# plugV15-smd-5x5cm-no-screen-value.net
KiCad netlist of a schematic drawn in EAGLE
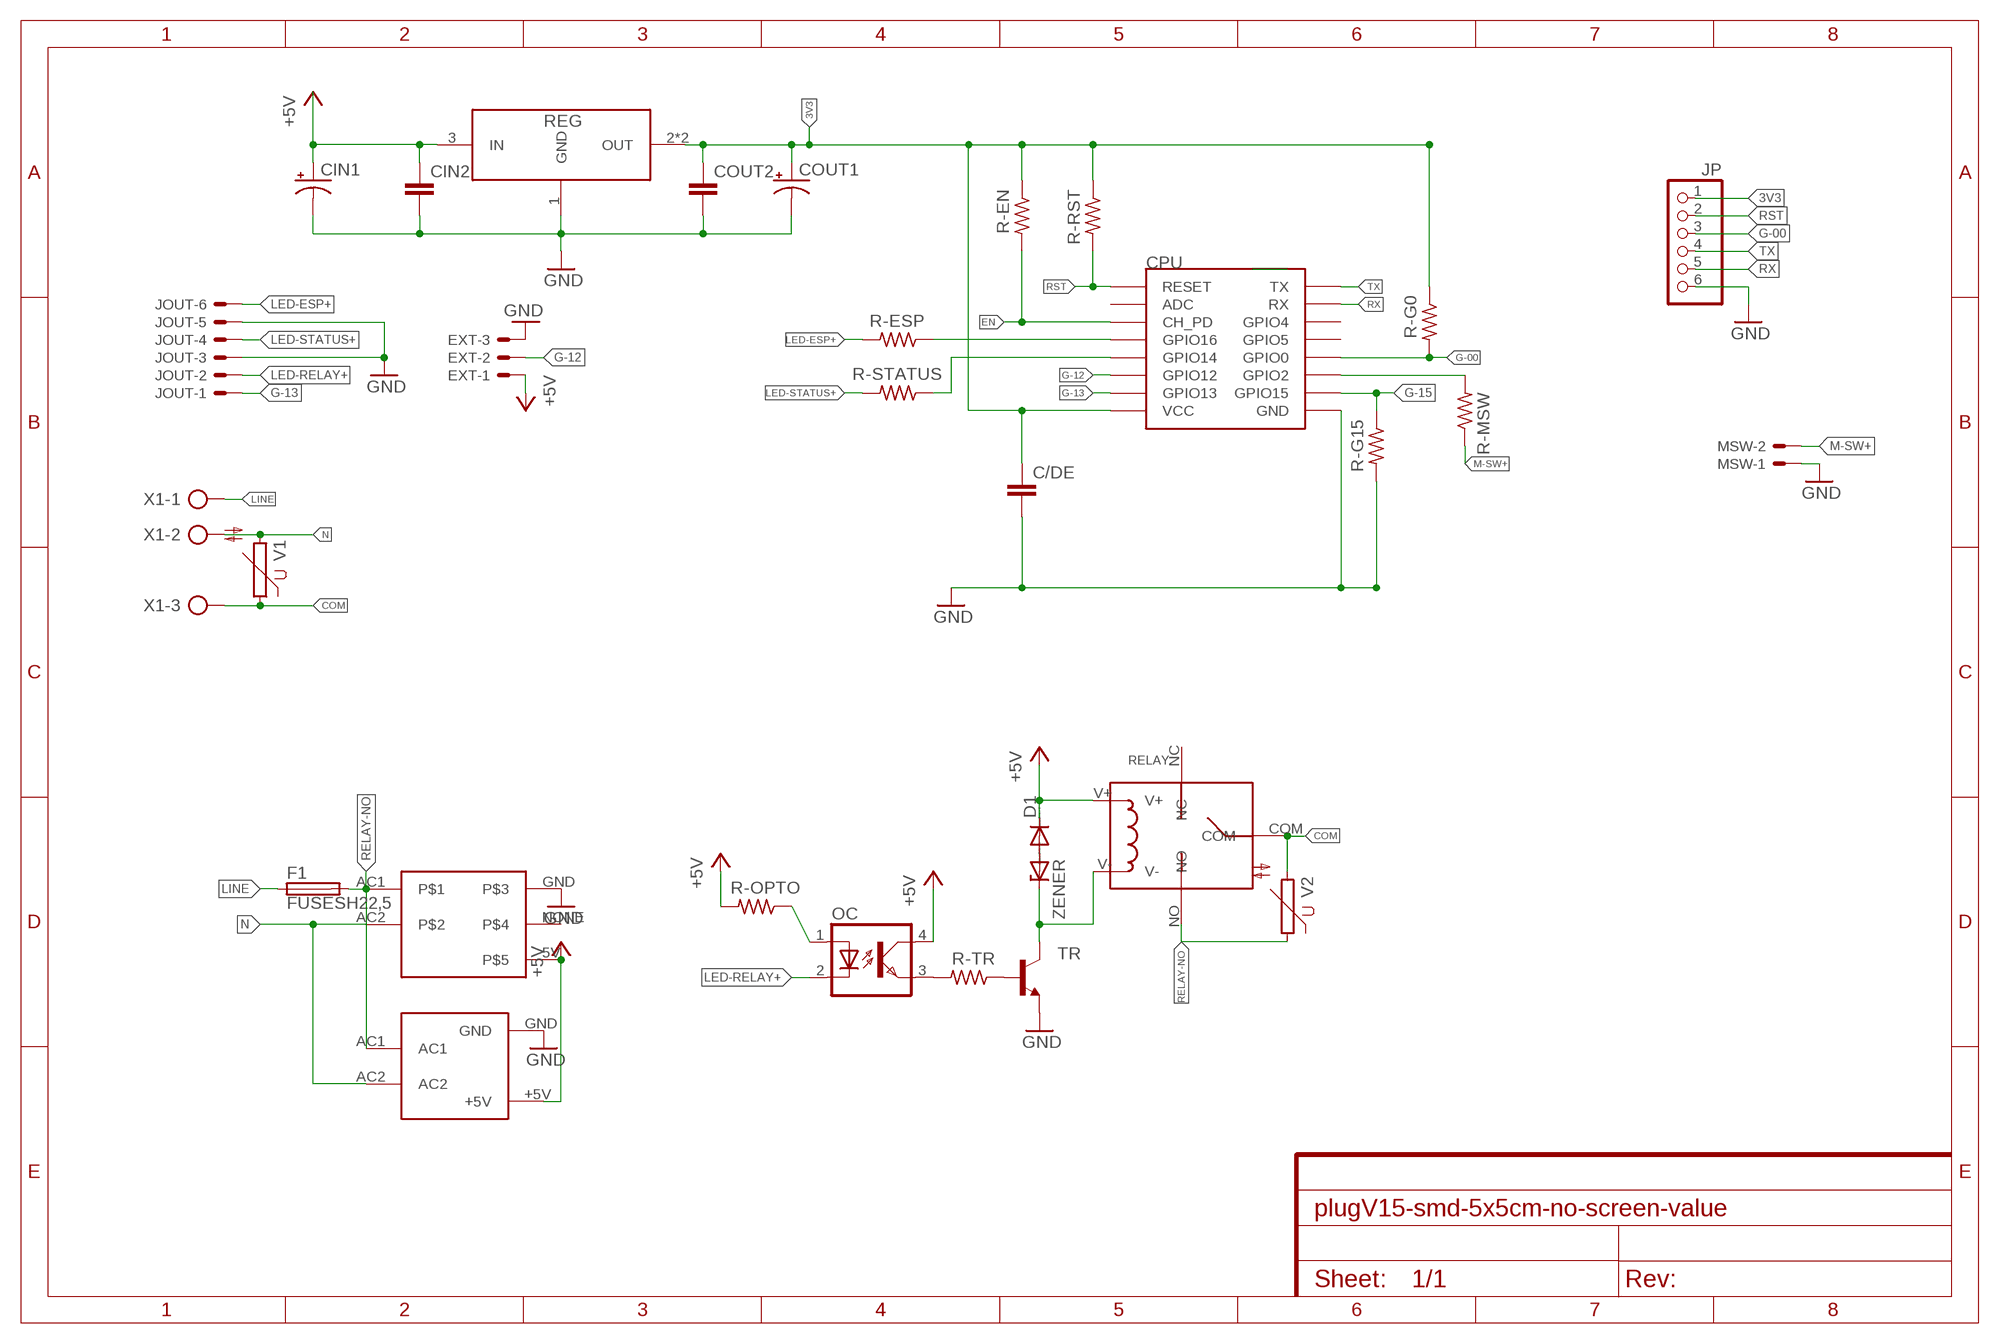
[diagram p0: schematic, sheet 1]

(export (version "E")
  (design (tool "Eeschema 10.0.6"))
  (components
    (comp (ref "C/DE")
      (value "C-EUC0805")
      (footprint "eagle-import:C0805")
      (libsource (lib "eagle-import") (part "C-EUC0805"))
    )
    (comp (ref "CIN1")
      (value "CPOL-USE2.5-5")
      (footprint "eagle-import:E2,5-5")
      (libsource (lib "eagle-import") (part "CPOL-USE2.5-5"))
    )
    (comp (ref "CIN2")
      (value "C-EUC0805")
      (footprint "eagle-import:C0805")
      (libsource (lib "eagle-import") (part "C-EUC0805"))
    )
    (comp (ref "COUT1")
      (value "CPOL-USE2.5-5")
      (footprint "eagle-import:E2,5-5")
      (libsource (lib "eagle-import") (part "CPOL-USE2.5-5"))
    )
    (comp (ref "COUT2")
      (value "C-EUC0805")
      (footprint "eagle-import:C0805")
      (libsource (lib "eagle-import") (part "C-EUC0805"))
    )
    (comp (ref "CPU")
      (value "ESP12SMD")
      (footprint "eagle-import:ESP12-SMD")
      (libsource (lib "eagle-import") (part "ESP12SMD"))
    )
    (comp (ref "D1")
      (value "1N4148DO35-7")
      (footprint "eagle-import:DO35-7")
      (libsource (lib "eagle-import") (part "1N4148DO35-7"))
    )
    (comp (ref "EXT")
      (value "53048-03")
      (footprint "eagle-import:53048-03")
      (fields (field (name "MF") "WALDOM/MOLEX") (field (name "MPN") "53048-0310"))
      (libsource (lib "eagle-import") (part "53?-03048"))
    )
    (comp (ref "F1")
      (value "FUSESH22,5")
      (footprint "eagle-import:SH22,5")
      (libsource (lib "eagle-import") (part "FUSESH22,5"))
    )
    (comp (ref "HLK")
      (value "HLK-PM01")
      (footprint "eagle-import:HLK-PM01")
      (libsource (lib "eagle-import") (part "HLK-PM01"))
    )
    (comp (ref "JOUT")
      (value "53048-06")
      (footprint "eagle-import:53048-06")
      (fields (field (name "MF") "WALDOM/MOLEX") (field (name "MPN") "53048-0610"))
      (libsource (lib "eagle-import") (part "53?-06048"))
    )
    (comp (ref "JP")
      (value "PINHD-1X6")
      (footprint "eagle-import:1X06")
      (libsource (lib "eagle-import") (part "PINHD-1X6"))
    )
    (comp (ref "MSW")
      (value "53048-02")
      (footprint "eagle-import:53048-02")
      (fields (field (name "MF") "MOLEX") (field (name "MPN") "53048-0210"))
      (libsource (lib "eagle-import") (part "53?-02048"))
    )
    (comp (ref "OC")
      (value "PC817")
      (footprint "eagle-import:DIL04")
      (fields (field (name "MPN") "PC817X4J000F"))
      (libsource (lib "eagle-import") (part "PC817"))
    )
    (comp (ref "R-EN")
      (value "R-US_M0805")
      (footprint "eagle-import:M0805")
      (libsource (lib "eagle-import") (part "R-US_M0805"))
    )
    (comp (ref "R-ESP")
      (value "R-US_M0805")
      (footprint "eagle-import:M0805")
      (libsource (lib "eagle-import") (part "R-US_M0805"))
    )
    (comp (ref "R-G0")
      (value "R-US_M0805")
      (footprint "eagle-import:M0805")
      (libsource (lib "eagle-import") (part "R-US_M0805"))
    )
    (comp (ref "R-G15")
      (value "R-US_M0805")
      (footprint "eagle-import:M0805")
      (libsource (lib "eagle-import") (part "R-US_M0805"))
    )
    (comp (ref "R-MSW")
      (value "R-US_M0805")
      (footprint "eagle-import:M0805")
      (libsource (lib "eagle-import") (part "R-US_M0805"))
    )
    (comp (ref "R-OPTO")
      (value "R-US_M0805")
      (footprint "eagle-import:M0805")
      (libsource (lib "eagle-import") (part "R-US_M0805"))
    )
    (comp (ref "R-RST")
      (value "R-US_M0805")
      (footprint "eagle-import:M0805")
      (libsource (lib "eagle-import") (part "R-US_M0805"))
    )
    (comp (ref "R-STATUS")
      (value "R-US_M0805")
      (footprint "eagle-import:M0805")
      (libsource (lib "eagle-import") (part "R-US_M0805"))
    )
    (comp (ref "R-TR")
      (value "R-US_M0805")
      (footprint "eagle-import:M0805")
      (libsource (lib "eagle-import") (part "R-US_M0805"))
    )
    (comp (ref "REG")
      (value "AMS1117-3.3")
      (footprint "eagle-import:SOT-223")
      (libsource (lib "eagle-import") (part "AMS1117-3.3"))
    )
    (comp (ref "RELAY")
      (value "RELAY-SONGLE")
      (footprint "eagle-import:RELAY-SONGLE")
      (libsource (lib "eagle-import") (part "RELAY-SONGLE"))
    )
    (comp (ref "TR")
      (value "BC817-16SMD")
      (footprint "eagle-import:SOT23-BEC")
      (libsource (lib "eagle-import") (part "BC817SMD-16"))
    )
    (comp (ref "U$4")
      (value "POWERSUPPLY-5V-700MA")
      (footprint "eagle-import:POWERSUPPLY-5V-700MA")
      (libsource (lib "eagle-import") (part "POWERSUPPLY-5V-700MA"))
    )
    (comp (ref "V1")
      (value "S14K11")
      (footprint "eagle-import:S14K11")
      (libsource (lib "eagle-import") (part "S14K11"))
    )
    (comp (ref "V2")
      (value "S14K11")
      (footprint "eagle-import:S14K11")
      (libsource (lib "eagle-import") (part "S14K11"))
    )
    (comp (ref "X1")
      (value "AK300/3")
      (footprint "eagle-import:AK300_3")
      (libsource (lib "eagle-import") (part "AK300/3"))
    )
    (comp (ref "ZENER")
      (value "1N4728")
      (footprint "eagle-import:DO41Z10")
      (libsource (lib "eagle-import") (part "1N4728"))
    )
  )
  (nets
    (net (code "1") (name "+5V") (class "Default")
      (node (ref "CIN1") (pin "+") (pinfunction "+_+") (pintype "passive"))
      (node (ref "CIN2") (pin "1") (pinfunction "1_1") (pintype "passive"))
      (node (ref "D1") (pin "C") (pinfunction "C_C") (pintype "passive"))
      (node (ref "EXT") (pin "1") (pinfunction "S_1") (pintype "passive"))
      (node (ref "HLK") (pin "+5V") (pinfunction "+5V_+5V") (pintype "bidirectional"))
      (node (ref "OC") (pin "4") (pinfunction "COL_4") (pintype "passive"))
      (node (ref "R-OPTO") (pin "2") (pinfunction "2_2") (pintype "passive"))
      (node (ref "REG") (pin "3") (pinfunction "IN_3") (pintype "input"))
      (node (ref "RELAY") (pin "V+") (pinfunction "V+_V+") (pintype "bidirectional"))
      (node (ref "U$4") (pin "5V") (pinfunction "P$5_5V") (pintype "bidirectional"))
    )
    (net (code "2") (name "3V3") (class "Default")
      (node (ref "C/DE") (pin "1") (pinfunction "1_1") (pintype "passive"))
      (node (ref "COUT1") (pin "+") (pinfunction "+_+") (pintype "passive"))
      (node (ref "COUT2") (pin "1") (pinfunction "1_1") (pintype "passive"))
      (node (ref "CPU") (pin "VCC") (pinfunction "VCC_VCC") (pintype "bidirectional"))
      (node (ref "JP") (pin "1") (pinfunction "1_1") (pintype "passive"))
      (node (ref "R-EN") (pin "1") (pinfunction "1_1") (pintype "passive"))
      (node (ref "R-G0") (pin "1") (pinfunction "1_1") (pintype "passive"))
      (node (ref "R-RST") (pin "1") (pinfunction "1_1") (pintype "passive"))
      (node (ref "REG") (pin "2") (pinfunction "OUT_2") (pintype "output"))
      (node (ref "REG") (pin "4") (pinfunction "OUT_4") (pintype "output"))
    )
    (net (code "3") (name "COM") (class "Default")
      (node (ref "RELAY") (pin "COM") (pinfunction "COM_COM") (pintype "bidirectional"))
      (node (ref "V1") (pin "1") (pinfunction "1_1") (pintype "passive"))
      (node (ref "V2") (pin "2") (pinfunction "2_2") (pintype "passive"))
      (node (ref "X1") (pin "3") (pinfunction "KL_3") (pintype "passive"))
    )
    (net (code "4") (name "EN") (class "Default")
      (node (ref "CPU") (pin "CH_PD") (pinfunction "CH_PD_CH_PD") (pintype "bidirectional"))
      (node (ref "R-EN") (pin "2") (pinfunction "2_2") (pintype "passive"))
    )
    (net (code "5") (name "G-00") (class "Default")
      (node (ref "CPU") (pin "GPIO0") (pinfunction "GPIO0_GPIO0") (pintype "bidirectional"))
      (node (ref "JP") (pin "3") (pinfunction "3_3") (pintype "passive"))
      (node (ref "R-G0") (pin "2") (pinfunction "2_2") (pintype "passive"))
    )
    (net (code "6") (name "G-12") (class "Default")
      (node (ref "CPU") (pin "GPIO12") (pinfunction "GPIO12_GPIO12") (pintype "bidirectional"))
      (node (ref "EXT") (pin "2") (pinfunction "S_2") (pintype "passive"))
    )
    (net (code "7") (name "G-13") (class "Default")
      (node (ref "CPU") (pin "GPIO13") (pinfunction "GPIO13_GPIO13") (pintype "bidirectional"))
      (node (ref "JOUT") (pin "1") (pinfunction "S_1") (pintype "passive"))
    )
    (net (code "8") (name "G-15") (class "Default")
      (node (ref "CPU") (pin "GPIO15") (pinfunction "GPIO15_GPIO15") (pintype "bidirectional"))
      (node (ref "R-G15") (pin "1") (pinfunction "1_1") (pintype "passive"))
    )
    (net (code "9") (name "GND") (class "Default")
      (node (ref "C/DE") (pin "2") (pinfunction "2_2") (pintype "passive"))
      (node (ref "CIN1") (pin "-") (pinfunction "-_-") (pintype "passive"))
      (node (ref "CIN2") (pin "2") (pinfunction "2_2") (pintype "passive"))
      (node (ref "COUT1") (pin "-") (pinfunction "-_-") (pintype "passive"))
      (node (ref "COUT2") (pin "2") (pinfunction "2_2") (pintype "passive"))
      (node (ref "CPU") (pin "GND") (pinfunction "GND_GND") (pintype "bidirectional"))
      (node (ref "EXT") (pin "3") (pinfunction "S_3") (pintype "passive"))
      (node (ref "HLK") (pin "GND") (pinfunction "GND_GND") (pintype "bidirectional"))
      (node (ref "JOUT") (pin "3") (pinfunction "S_3") (pintype "passive"))
      (node (ref "JOUT") (pin "5") (pinfunction "S_5") (pintype "passive"))
      (node (ref "JP") (pin "6") (pinfunction "6_6") (pintype "passive"))
      (node (ref "MSW") (pin "1") (pinfunction "S_1") (pintype "passive"))
      (node (ref "R-G15") (pin "2") (pinfunction "2_2") (pintype "passive"))
      (node (ref "REG") (pin "1") (pinfunction "GND_1") (pintype "passive"))
      (node (ref "TR") (pin "E") (pinfunction "E_E") (pintype "passive"))
      (node (ref "U$4") (pin "GND") (pinfunction "P$3_GND") (pintype "bidirectional"))
    )
    (net (code "10") (name "LED-ESP+") (class "Default")
      (node (ref "JOUT") (pin "6") (pinfunction "S_6") (pintype "passive"))
      (node (ref "R-ESP") (pin "2") (pinfunction "2_2") (pintype "passive"))
    )
    (net (code "11") (name "LED-RELAY+") (class "Default")
      (node (ref "JOUT") (pin "2") (pinfunction "S_2") (pintype "passive"))
      (node (ref "OC") (pin "2") (pinfunction "C_2") (pintype "passive"))
    )
    (net (code "12") (name "LED-STATUS+") (class "Default")
      (node (ref "JOUT") (pin "4") (pinfunction "S_4") (pintype "passive"))
      (node (ref "R-STATUS") (pin "2") (pinfunction "2_2") (pintype "passive"))
    )
    (net (code "13") (name "LINE") (class "Default")
      (node (ref "F1") (pin "1") (pinfunction "1_1") (pintype "passive"))
      (node (ref "X1") (pin "1") (pinfunction "KL_1") (pintype "passive"))
    )
    (net (code "14") (name "M-SW+") (class "Default")
      (node (ref "MSW") (pin "2") (pinfunction "S_2") (pintype "passive"))
      (node (ref "R-MSW") (pin "1") (pinfunction "1_1") (pintype "passive"))
    )
    (net (code "15") (name "N") (class "Default")
      (node (ref "HLK") (pin "AC2") (pinfunction "AC2_AC2") (pintype "bidirectional"))
      (node (ref "U$4") (pin "AC2") (pinfunction "P$2_AC2") (pintype "bidirectional"))
      (node (ref "V1") (pin "2") (pinfunction "2_2") (pintype "passive"))
      (node (ref "X1") (pin "2") (pinfunction "KL_2") (pintype "passive"))
    )
    (net (code "16") (name "Net-(CPU-PadGPIO2)") (class "Default")
      (node (ref "CPU") (pin "GPIO2") (pinfunction "GPIO2_GPIO2") (pintype "bidirectional"))
      (node (ref "R-MSW") (pin "2") (pinfunction "2_2") (pintype "passive"))
    )
    (net (code "17") (name "Net-(CPU-PadGPIO14)") (class "Default")
      (node (ref "CPU") (pin "GPIO14") (pinfunction "GPIO14_GPIO14") (pintype "bidirectional"))
      (node (ref "R-STATUS") (pin "1") (pinfunction "1_1") (pintype "passive"))
    )
    (net (code "18") (name "Net-(CPU-PadGPIO16)") (class "Default")
      (node (ref "CPU") (pin "GPIO16") (pinfunction "GPIO16_GPIO16") (pintype "bidirectional"))
      (node (ref "R-ESP") (pin "1") (pinfunction "1_1") (pintype "passive"))
    )
    (net (code "19") (name "Net-(D1-PadA)") (class "Default")
      (node (ref "D1") (pin "A") (pinfunction "A_A") (pintype "passive"))
      (node (ref "ZENER") (pin "A") (pinfunction "A_A") (pintype "passive"))
    )
    (net (code "20") (name "Net-(OC-A)") (class "Default")
      (node (ref "OC") (pin "1") (pinfunction "A_1") (pintype "passive"))
      (node (ref "R-OPTO") (pin "1") (pinfunction "1_1") (pintype "passive"))
    )
    (net (code "21") (name "Net-(OC-EMIT)") (class "Default")
      (node (ref "OC") (pin "3") (pinfunction "EMIT_3") (pintype "passive"))
      (node (ref "R-TR") (pin "2") (pinfunction "2_2") (pintype "passive"))
    )
    (net (code "22") (name "Net-(R-TR-Pad1)") (class "Default")
      (node (ref "R-TR") (pin "1") (pinfunction "1_1") (pintype "passive"))
      (node (ref "TR") (pin "B") (pinfunction "B_B") (pintype "passive"))
    )
    (net (code "23") (name "Net-(RELAY-PadV-)") (class "Default")
      (node (ref "RELAY") (pin "V-") (pinfunction "V-_V-") (pintype "bidirectional"))
      (node (ref "TR") (pin "C") (pinfunction "C_C") (pintype "passive"))
      (node (ref "ZENER") (pin "C") (pinfunction "C_C") (pintype "passive"))
    )
    (net (code "24") (name "RELAY-NO") (class "Default")
      (node (ref "F1") (pin "2") (pinfunction "2_2") (pintype "passive"))
      (node (ref "HLK") (pin "AC1") (pinfunction "AC1_AC1") (pintype "bidirectional"))
      (node (ref "RELAY") (pin "NO") (pinfunction "NO_NO") (pintype "bidirectional"))
      (node (ref "U$4") (pin "AC1") (pinfunction "P$1_AC1") (pintype "bidirectional"))
      (node (ref "V2") (pin "1") (pinfunction "1_1") (pintype "passive"))
    )
    (net (code "25") (name "RST") (class "Default")
      (node (ref "CPU") (pin "RESET") (pinfunction "RESET_RESET") (pintype "bidirectional"))
      (node (ref "JP") (pin "2") (pinfunction "2_2") (pintype "passive"))
      (node (ref "R-RST") (pin "2") (pinfunction "2_2") (pintype "passive"))
    )
    (net (code "26") (name "RX") (class "Default")
      (node (ref "CPU") (pin "RXD0") (pinfunction "RX_RXD0") (pintype "bidirectional"))
      (node (ref "JP") (pin "5") (pinfunction "5_5") (pintype "passive"))
    )
    (net (code "27") (name "TX") (class "Default")
      (node (ref "CPU") (pin "TXD0") (pinfunction "TX_TXD0") (pintype "bidirectional"))
      (node (ref "JP") (pin "4") (pinfunction "4_4") (pintype "passive"))
    )
    (net (code "28") (name "unconnected-(CPU-PadADC)") (class "Default")
      (node (ref "CPU") (pin "ADC") (pinfunction "ADC_ADC") (pintype "bidirectional"))
    )
    (net (code "29") (name "unconnected-(CPU-PadGPIO4)") (class "Default")
      (node (ref "CPU") (pin "GPIO4") (pinfunction "GPIO4_GPIO4") (pintype "bidirectional"))
    )
    (net (code "30") (name "unconnected-(CPU-PadGPIO5)") (class "Default")
      (node (ref "CPU") (pin "GPIO5") (pinfunction "GPIO5_GPIO5") (pintype "bidirectional"))
    )
    (net (code "31") (name "unconnected-(RELAY-PadNC)") (class "Default")
      (node (ref "RELAY") (pin "NC") (pinfunction "NC_NC") (pintype "bidirectional"))
    )
    (net (code "32") (name "unconnected-(U$4-P$4-PadNONE)") (class "Default")
      (node (ref "U$4") (pin "NONE") (pinfunction "P$4_NONE") (pintype "bidirectional"))
    )
  )
)
